# Connectors.net
KiCad netlist of a schematic drawn in Altium Designer
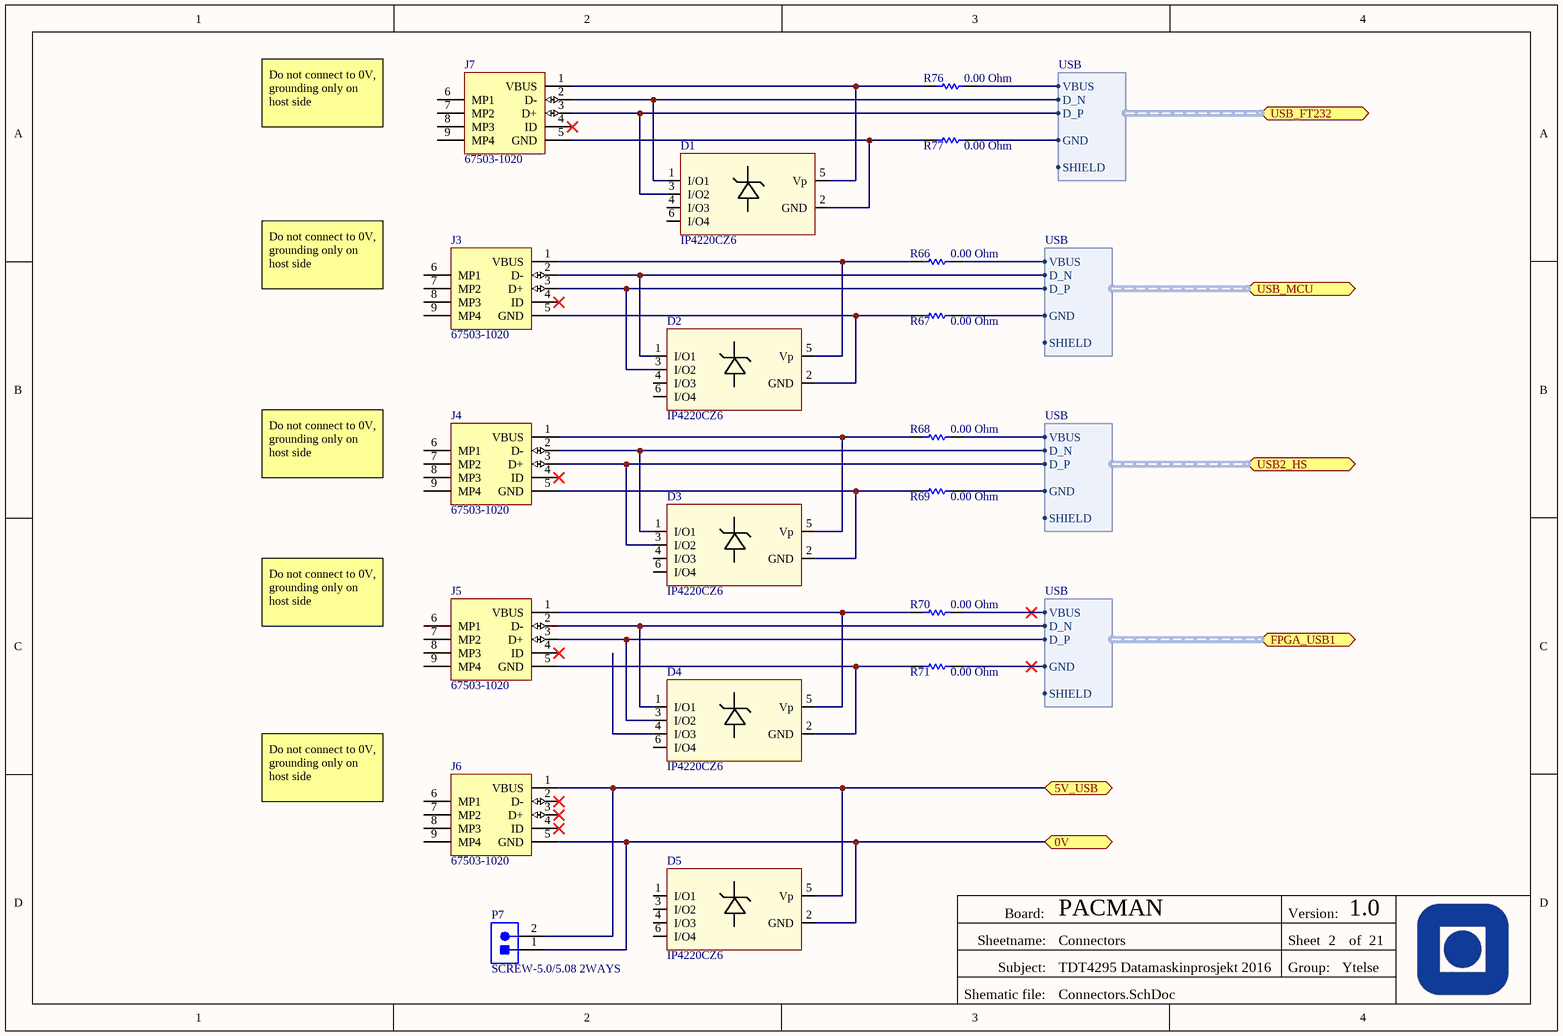
[diagram p0: Connectors.SchDoc]

(export (version "E")
  (design (tool "Eeschema 10.0.6"))
  (components
    (comp (ref "D1")
      (value "IP4220CZ6")
      (footprint "NXP SOT457")
      (description "4 channel USB ESD protection device")
      (libsource (lib "dmpro16lib") (part "IP4220CZ6"))
    )
    (comp (ref "D2")
      (value "IP4220CZ6")
      (footprint "NXP SOT457")
      (description "4 channel USB ESD protection device")
      (libsource (lib "dmpro16lib") (part "IP4220CZ6"))
    )
    (comp (ref "D3")
      (value "IP4220CZ6")
      (footprint "NXP SOT457")
      (description "4 channel USB ESD protection device")
      (libsource (lib "dmpro16lib") (part "IP4220CZ6"))
    )
    (comp (ref "D4")
      (value "IP4220CZ6")
      (footprint "NXP SOT457")
      (description "4 channel USB ESD protection device")
      (libsource (lib "dmpro16lib") (part "IP4220CZ6"))
    )
    (comp (ref "D5")
      (value "IP4220CZ6")
      (footprint "NXP SOT457")
      (description "4 channel USB ESD protection device")
      (libsource (lib "dmpro16lib") (part "IP4220CZ6"))
    )
    (comp (ref "J3")
      (value "67503-1020")
      (footprint "MOLX-67503-1020_V")
      (description "USB, MINI, SMD, RA KME04-USBMU03A01")
      (fields (field (name "MANUFACTURER") "Molex"))
      (libsource (lib "Altium Content Vault") (part "MOLX-67503-1020"))
    )
    (comp (ref "J4")
      (value "67503-1020")
      (footprint "MOLX-67503-1020_V")
      (description "USB, MINI, SMD, RA KME04-USBMU03A01")
      (fields (field (name "MANUFACTURER") "Molex"))
      (libsource (lib "Altium Content Vault") (part "MOLX-67503-1020"))
    )
    (comp (ref "J5")
      (value "67503-1020")
      (footprint "MOLX-67503-1020_V")
      (description "USB, MINI, SMD, RA KME04-USBMU03A01")
      (fields (field (name "MANUFACTURER") "Molex"))
      (libsource (lib "Altium Content Vault") (part "MOLX-67503-1020"))
    )
    (comp (ref "J6")
      (value "67503-1020")
      (footprint "MOLX-67503-1020_V")
      (description "USB, MINI, SMD, RA KME04-USBMU03A01")
      (fields (field (name "MANUFACTURER") "Molex"))
      (libsource (lib "Altium Content Vault") (part "MOLX-67503-1020"))
    )
    (comp (ref "J7")
      (value "67503-1020")
      (footprint "MOLX-67503-1020_V")
      (description "USB, MINI, SMD, RA KME04-USBMU03A01")
      (fields (field (name "MANUFACTURER") "Molex"))
      (libsource (lib "Altium Content Vault") (part "MOLX-67503-1020"))
    )
    (comp (ref "P7")
      (value "SCREW-5.0/5.08 2WAYS")
      (footprint "SCREW-5.0-2WAYS_V")
      (description "Socket, Screw Terminal Block, 2 Way, 5.0 mm Pitch, 90 Degree Angle, Through-Hole")
      (fields (field (name "MANUFACTURER") "No Vendor"))
      (libsource (lib "Altium Content Vault") (part "SCREW-2WAYS"))
    )
    (comp (ref "R66")
      (value "0.00 Ohm")
      (footprint "RESC0603(1608)_N")
      (description "Jumper 0603 (1608 Metric)")
      (fields (field (name "POWER") "None") (field (name "Comment") "Jumper 0603(1608)"))
      (libsource (lib "Altium Content Vault") (part "CMP-1012-00001-1"))
    )
    (comp (ref "R67")
      (value "0.00 Ohm")
      (footprint "RESC0603(1608)_N")
      (description "Jumper 0603 (1608 Metric)")
      (fields (field (name "POWER") "None") (field (name "Comment") "Jumper 0603(1608)"))
      (libsource (lib "Altium Content Vault") (part "CMP-1012-00001-1"))
    )
    (comp (ref "R68")
      (value "0.00 Ohm")
      (footprint "RESC0603(1608)_N")
      (description "Jumper 0603 (1608 Metric)")
      (fields (field (name "POWER") "None") (field (name "Comment") "Jumper 0603(1608)"))
      (libsource (lib "Altium Content Vault") (part "CMP-1012-00001-1"))
    )
    (comp (ref "R69")
      (value "0.00 Ohm")
      (footprint "RESC0603(1608)_N")
      (description "Jumper 0603 (1608 Metric)")
      (fields (field (name "POWER") "None") (field (name "Comment") "Jumper 0603(1608)"))
      (libsource (lib "Altium Content Vault") (part "CMP-1012-00001-1"))
    )
    (comp (ref "R70")
      (value "0.00 Ohm")
      (footprint "RESC0603(1608)_N")
      (description "Jumper 0603 (1608 Metric)")
      (fields (field (name "POWER") "None") (field (name "Comment") "Jumper 0603(1608)"))
      (libsource (lib "Altium Content Vault") (part "CMP-1012-00001-1"))
    )
    (comp (ref "R71")
      (value "0.00 Ohm")
      (footprint "RESC0603(1608)_N")
      (description "Jumper 0603 (1608 Metric)")
      (fields (field (name "POWER") "None") (field (name "Comment") "Jumper 0603(1608)"))
      (libsource (lib "Altium Content Vault") (part "CMP-1012-00001-1"))
    )
    (comp (ref "R76")
      (value "0.00 Ohm")
      (footprint "RESC0603(1608)_N")
      (description "Jumper 0603 (1608 Metric)")
      (fields (field (name "POWER") "None") (field (name "Comment") "Jumper 0603(1608)"))
      (libsource (lib "Altium Content Vault") (part "CMP-1012-00001-1"))
    )
    (comp (ref "R77")
      (value "0.00 Ohm")
      (footprint "RESC0603(1608)_N")
      (description "Jumper 0603 (1608 Metric)")
      (fields (field (name "POWER") "None") (field (name "Comment") "Jumper 0603(1608)"))
      (libsource (lib "Altium Content Vault") (part "CMP-1012-00001-1"))
    )
  )
  (nets
    (net (code "2") (name "/0V") (class "Default")
      (node (ref "D5") (pin "2") (pinfunction "GND_2") (pintype "passive"))
      (node (ref "J6") (pin "5") (pinfunction "GND_5") (pintype "power_in"))
      (node (ref "P7") (pin "1") (pinfunction "1_1") (pintype "passive"))
    )
    (net (code "3") (name "/5V_USB") (class "Default")
      (node (ref "D5") (pin "5") (pinfunction "Vp_5") (pintype "passive"))
      (node (ref "J6") (pin "1") (pinfunction "VBUS_1") (pintype "power_in"))
      (node (ref "P7") (pin "2") (pinfunction "2_2") (pintype "passive"))
    )
    (net (code "5") (name "Net-(D1-GND)") (class "Default")
      (node (ref "D1") (pin "2") (pinfunction "GND_2") (pintype "passive"))
      (node (ref "J7") (pin "5") (pinfunction "GND_5") (pintype "power_in"))
      (node (ref "R77") (pin "1") (pinfunction "1_1") (pintype "passive"))
    )
    (net (code "6") (name "Net-(D1-I{slash}O1)") (class "Default")
      (node (ref "D1") (pin "1") (pinfunction "I/O1_1") (pintype "passive"))
      (node (ref "J7") (pin "2") (pinfunction "D-_2") (pintype "bidirectional"))
    )
    (net (code "7") (name "Net-(D1-I{slash}O2)") (class "Default")
      (node (ref "D1") (pin "3") (pinfunction "I/O2_3") (pintype "passive"))
      (node (ref "J7") (pin "3") (pinfunction "D+_3") (pintype "bidirectional"))
    )
    (net (code "8") (name "Net-(D1-Vp)") (class "Default")
      (node (ref "D1") (pin "5") (pinfunction "Vp_5") (pintype "passive"))
      (node (ref "J7") (pin "1") (pinfunction "VBUS_1") (pintype "power_in"))
      (node (ref "R76") (pin "1") (pinfunction "1_1") (pintype "passive"))
    )
    (net (code "9") (name "Net-(D2-GND)") (class "Default")
      (node (ref "D2") (pin "2") (pinfunction "GND_2") (pintype "passive"))
      (node (ref "J3") (pin "5") (pinfunction "GND_5") (pintype "power_in"))
      (node (ref "R67") (pin "1") (pinfunction "1_1") (pintype "passive"))
    )
    (net (code "10") (name "Net-(D2-I{slash}O1)") (class "Default")
      (node (ref "D2") (pin "1") (pinfunction "I/O1_1") (pintype "passive"))
      (node (ref "J3") (pin "2") (pinfunction "D-_2") (pintype "bidirectional"))
    )
    (net (code "11") (name "Net-(D2-I{slash}O2)") (class "Default")
      (node (ref "D2") (pin "3") (pinfunction "I/O2_3") (pintype "passive"))
      (node (ref "J3") (pin "3") (pinfunction "D+_3") (pintype "bidirectional"))
    )
    (net (code "12") (name "Net-(D2-Vp)") (class "Default")
      (node (ref "D2") (pin "5") (pinfunction "Vp_5") (pintype "passive"))
      (node (ref "J3") (pin "1") (pinfunction "VBUS_1") (pintype "power_in"))
      (node (ref "R66") (pin "1") (pinfunction "1_1") (pintype "passive"))
    )
    (net (code "13") (name "Net-(D3-GND)") (class "Default")
      (node (ref "D3") (pin "2") (pinfunction "GND_2") (pintype "passive"))
      (node (ref "J4") (pin "5") (pinfunction "GND_5") (pintype "power_in"))
      (node (ref "R69") (pin "1") (pinfunction "1_1") (pintype "passive"))
    )
    (net (code "14") (name "Net-(D3-I{slash}O1)") (class "Default")
      (node (ref "D3") (pin "1") (pinfunction "I/O1_1") (pintype "passive"))
      (node (ref "J4") (pin "2") (pinfunction "D-_2") (pintype "bidirectional"))
    )
    (net (code "15") (name "Net-(D3-I{slash}O2)") (class "Default")
      (node (ref "D3") (pin "3") (pinfunction "I/O2_3") (pintype "passive"))
      (node (ref "J4") (pin "3") (pinfunction "D+_3") (pintype "bidirectional"))
    )
    (net (code "16") (name "Net-(D3-Vp)") (class "Default")
      (node (ref "D3") (pin "5") (pinfunction "Vp_5") (pintype "passive"))
      (node (ref "J4") (pin "1") (pinfunction "VBUS_1") (pintype "power_in"))
      (node (ref "R68") (pin "1") (pinfunction "1_1") (pintype "passive"))
    )
    (net (code "17") (name "Net-(D4-GND)") (class "Default")
      (node (ref "D4") (pin "2") (pinfunction "GND_2") (pintype "passive"))
      (node (ref "J5") (pin "5") (pinfunction "GND_5") (pintype "power_in"))
      (node (ref "R71") (pin "1") (pinfunction "1_1") (pintype "passive"))
    )
    (net (code "18") (name "Net-(D4-I{slash}O1)") (class "Default")
      (node (ref "D4") (pin "1") (pinfunction "I/O1_1") (pintype "passive"))
      (node (ref "J5") (pin "2") (pinfunction "D-_2") (pintype "bidirectional"))
    )
    (net (code "19") (name "Net-(D4-I{slash}O2)") (class "Default")
      (node (ref "D4") (pin "3") (pinfunction "I/O2_3") (pintype "passive"))
      (node (ref "J5") (pin "3") (pinfunction "D+_3") (pintype "bidirectional"))
    )
    (net (code "20") (name "Net-(D4-Vp)") (class "Default")
      (node (ref "D4") (pin "5") (pinfunction "Vp_5") (pintype "passive"))
      (node (ref "J5") (pin "1") (pinfunction "VBUS_1") (pintype "power_in"))
      (node (ref "R70") (pin "1") (pinfunction "1_1") (pintype "passive"))
    )
    (net (code "21") (name "unconnected-(D1-I{slash}O3-Pad4)") (class "Default")
      (node (ref "D1") (pin "4") (pinfunction "I/O3_4") (pintype "passive"))
    )
    (net (code "22") (name "unconnected-(D1-I{slash}O4-Pad6)") (class "Default")
      (node (ref "D1") (pin "6") (pinfunction "I/O4_6") (pintype "passive"))
    )
    (net (code "23") (name "unconnected-(D2-I{slash}O3-Pad4)") (class "Default")
      (node (ref "D2") (pin "4") (pinfunction "I/O3_4") (pintype "passive"))
    )
    (net (code "24") (name "unconnected-(D2-I{slash}O4-Pad6)") (class "Default")
      (node (ref "D2") (pin "6") (pinfunction "I/O4_6") (pintype "passive"))
    )
    (net (code "25") (name "unconnected-(D3-I{slash}O3-Pad4)") (class "Default")
      (node (ref "D3") (pin "4") (pinfunction "I/O3_4") (pintype "passive"))
    )
    (net (code "26") (name "unconnected-(D3-I{slash}O4-Pad6)") (class "Default")
      (node (ref "D3") (pin "6") (pinfunction "I/O4_6") (pintype "passive"))
    )
    (net (code "27") (name "unconnected-(D4-I{slash}O3-Pad4)") (class "Default")
      (node (ref "D4") (pin "4") (pinfunction "I/O3_4") (pintype "passive"))
    )
    (net (code "28") (name "unconnected-(D4-I{slash}O4-Pad6)") (class "Default")
      (node (ref "D4") (pin "6") (pinfunction "I/O4_6") (pintype "passive"))
    )
    (net (code "29") (name "unconnected-(D5-I{slash}O1-Pad1)") (class "Default")
      (node (ref "D5") (pin "1") (pinfunction "I/O1_1") (pintype "passive"))
    )
    (net (code "30") (name "unconnected-(D5-I{slash}O2-Pad3)") (class "Default")
      (node (ref "D5") (pin "3") (pinfunction "I/O2_3") (pintype "passive"))
    )
    (net (code "31") (name "unconnected-(D5-I{slash}O3-Pad4)") (class "Default")
      (node (ref "D5") (pin "4") (pinfunction "I/O3_4") (pintype "passive"))
    )
    (net (code "32") (name "unconnected-(D5-I{slash}O4-Pad6)") (class "Default")
      (node (ref "D5") (pin "6") (pinfunction "I/O4_6") (pintype "passive"))
    )
    (net (code "33") (name "unconnected-(J3-ID-Pad4)") (class "Default")
      (node (ref "J3") (pin "4") (pinfunction "ID_4") (pintype "passive+no_connect"))
    )
    (net (code "34") (name "unconnected-(J3-MP1-Pad6)") (class "Default")
      (node (ref "J3") (pin "6") (pinfunction "MP1_6") (pintype "passive"))
    )
    (net (code "35") (name "unconnected-(J3-MP2-Pad7)") (class "Default")
      (node (ref "J3") (pin "7") (pinfunction "MP2_7") (pintype "passive"))
    )
    (net (code "36") (name "unconnected-(J3-MP3-Pad8)") (class "Default")
      (node (ref "J3") (pin "8") (pinfunction "MP3_8") (pintype "passive"))
    )
    (net (code "37") (name "unconnected-(J3-MP4-Pad9)") (class "Default")
      (node (ref "J3") (pin "9") (pinfunction "MP4_9") (pintype "passive"))
    )
    (net (code "38") (name "unconnected-(J4-ID-Pad4)") (class "Default")
      (node (ref "J4") (pin "4") (pinfunction "ID_4") (pintype "passive+no_connect"))
    )
    (net (code "39") (name "unconnected-(J4-MP1-Pad6)") (class "Default")
      (node (ref "J4") (pin "6") (pinfunction "MP1_6") (pintype "passive"))
    )
    (net (code "40") (name "unconnected-(J4-MP2-Pad7)") (class "Default")
      (node (ref "J4") (pin "7") (pinfunction "MP2_7") (pintype "passive"))
    )
    (net (code "41") (name "unconnected-(J4-MP3-Pad8)") (class "Default")
      (node (ref "J4") (pin "8") (pinfunction "MP3_8") (pintype "passive"))
    )
    (net (code "42") (name "unconnected-(J4-MP4-Pad9)") (class "Default")
      (node (ref "J4") (pin "9") (pinfunction "MP4_9") (pintype "passive"))
    )
    (net (code "43") (name "unconnected-(J5-ID-Pad4)") (class "Default")
      (node (ref "J5") (pin "4") (pinfunction "ID_4") (pintype "passive+no_connect"))
    )
    (net (code "44") (name "unconnected-(J5-MP1-Pad6)") (class "Default")
      (node (ref "J5") (pin "6") (pinfunction "MP1_6") (pintype "passive"))
    )
    (net (code "45") (name "unconnected-(J5-MP2-Pad7)") (class "Default")
      (node (ref "J5") (pin "7") (pinfunction "MP2_7") (pintype "passive"))
    )
    (net (code "46") (name "unconnected-(J5-MP3-Pad8)") (class "Default")
      (node (ref "J5") (pin "8") (pinfunction "MP3_8") (pintype "passive"))
    )
    (net (code "47") (name "unconnected-(J5-MP4-Pad9)") (class "Default")
      (node (ref "J5") (pin "9") (pinfunction "MP4_9") (pintype "passive"))
    )
    (net (code "48") (name "unconnected-(J6-D+-Pad3)") (class "Default")
      (node (ref "J6") (pin "3") (pinfunction "D+_3") (pintype "bidirectional+no_connect"))
    )
    (net (code "49") (name "unconnected-(J6-D--Pad2)") (class "Default")
      (node (ref "J6") (pin "2") (pinfunction "D-_2") (pintype "bidirectional+no_connect"))
    )
    (net (code "50") (name "unconnected-(J6-ID-Pad4)") (class "Default")
      (node (ref "J6") (pin "4") (pinfunction "ID_4") (pintype "passive+no_connect"))
    )
    (net (code "51") (name "unconnected-(J6-MP1-Pad6)") (class "Default")
      (node (ref "J6") (pin "6") (pinfunction "MP1_6") (pintype "passive"))
    )
    (net (code "52") (name "unconnected-(J6-MP2-Pad7)") (class "Default")
      (node (ref "J6") (pin "7") (pinfunction "MP2_7") (pintype "passive"))
    )
    (net (code "53") (name "unconnected-(J6-MP3-Pad8)") (class "Default")
      (node (ref "J6") (pin "8") (pinfunction "MP3_8") (pintype "passive"))
    )
    (net (code "54") (name "unconnected-(J6-MP4-Pad9)") (class "Default")
      (node (ref "J6") (pin "9") (pinfunction "MP4_9") (pintype "passive"))
    )
    (net (code "55") (name "unconnected-(J7-ID-Pad4)") (class "Default")
      (node (ref "J7") (pin "4") (pinfunction "ID_4") (pintype "passive+no_connect"))
    )
    (net (code "56") (name "unconnected-(J7-MP1-Pad6)") (class "Default")
      (node (ref "J7") (pin "6") (pinfunction "MP1_6") (pintype "passive"))
    )
    (net (code "57") (name "unconnected-(J7-MP2-Pad7)") (class "Default")
      (node (ref "J7") (pin "7") (pinfunction "MP2_7") (pintype "passive"))
    )
    (net (code "58") (name "unconnected-(J7-MP3-Pad8)") (class "Default")
      (node (ref "J7") (pin "8") (pinfunction "MP3_8") (pintype "passive"))
    )
    (net (code "59") (name "unconnected-(J7-MP4-Pad9)") (class "Default")
      (node (ref "J7") (pin "9") (pinfunction "MP4_9") (pintype "passive"))
    )
    (net (code "60") (name "unconnected-(R66-Pad2)") (class "Default")
      (node (ref "R66") (pin "2") (pinfunction "2_2") (pintype "passive"))
    )
    (net (code "61") (name "unconnected-(R67-Pad2)") (class "Default")
      (node (ref "R67") (pin "2") (pinfunction "2_2") (pintype "passive"))
    )
    (net (code "62") (name "unconnected-(R68-Pad2)") (class "Default")
      (node (ref "R68") (pin "2") (pinfunction "2_2") (pintype "passive"))
    )
    (net (code "63") (name "unconnected-(R69-Pad2)") (class "Default")
      (node (ref "R69") (pin "2") (pinfunction "2_2") (pintype "passive"))
    )
    (net (code "64") (name "unconnected-(R70-Pad2)") (class "Default")
      (node (ref "R70") (pin "2") (pinfunction "2_2") (pintype "passive"))
    )
    (net (code "65") (name "unconnected-(R71-Pad2)") (class "Default")
      (node (ref "R71") (pin "2") (pinfunction "2_2") (pintype "passive"))
    )
    (net (code "66") (name "unconnected-(R76-Pad2)") (class "Default")
      (node (ref "R76") (pin "2") (pinfunction "2_2") (pintype "passive"))
    )
    (net (code "67") (name "unconnected-(R77-Pad2)") (class "Default")
      (node (ref "R77") (pin "2") (pinfunction "2_2") (pintype "passive"))
    )
  )
)
